# SH3-CONTROLS.net
KiCad netlist of a schematic drawn in Altium Designer
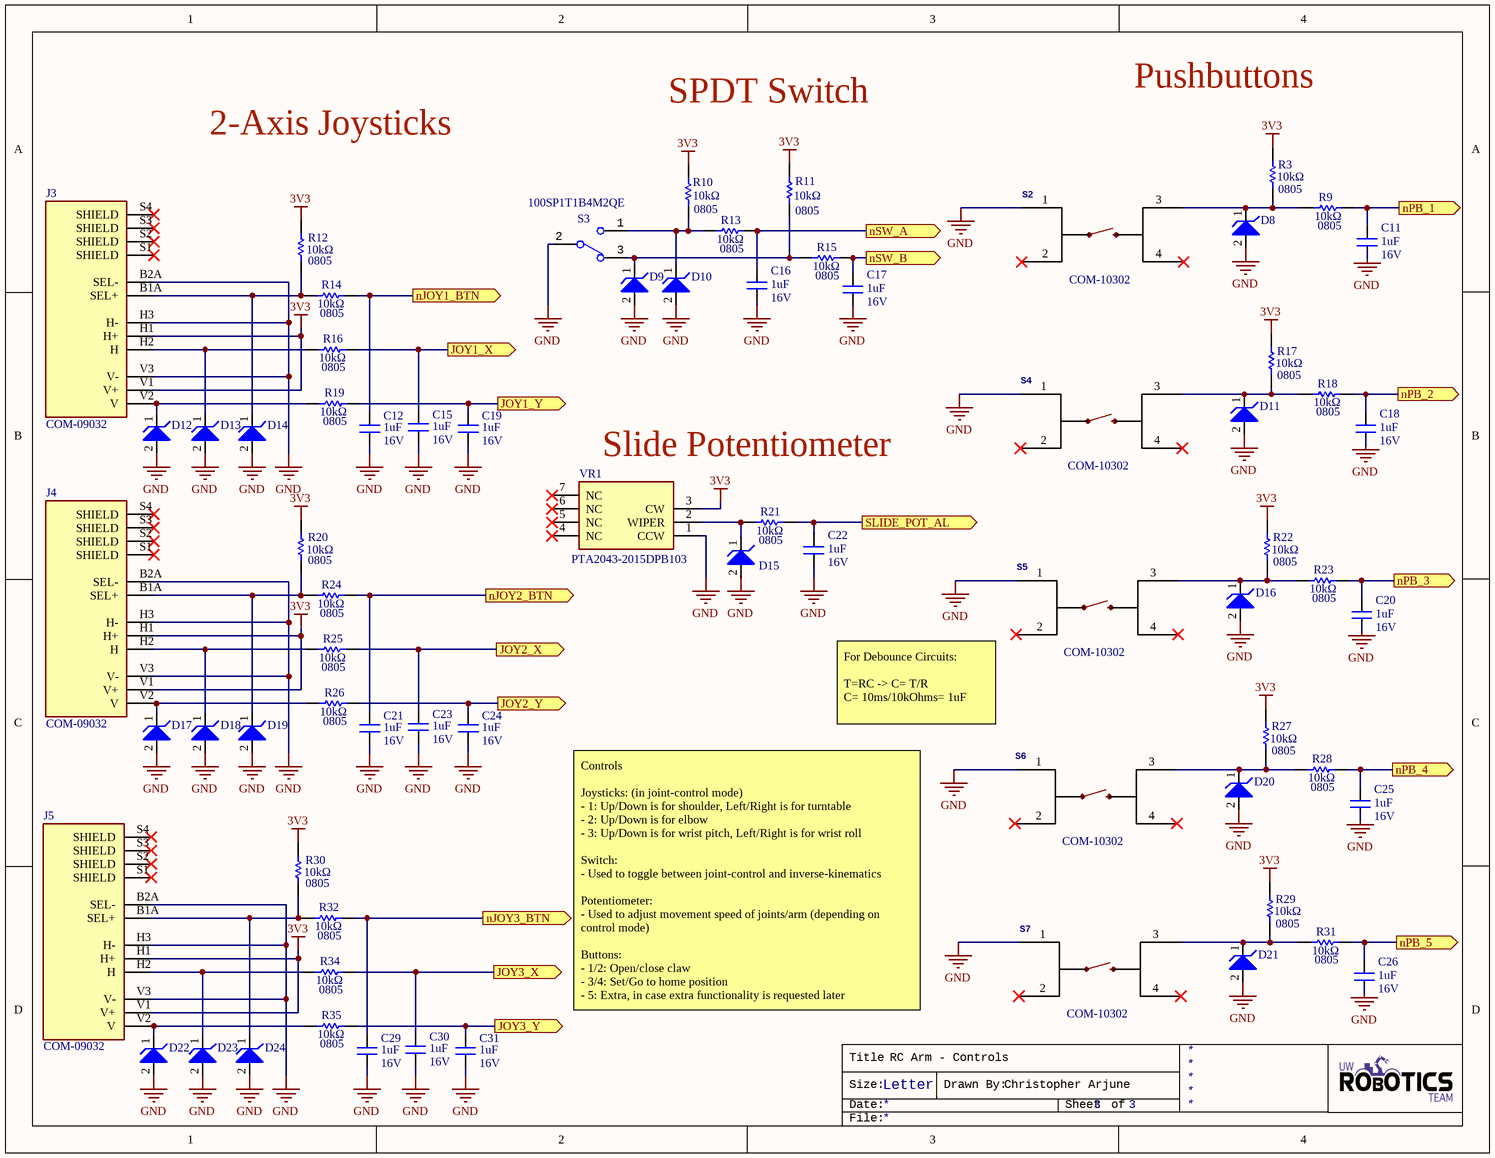
[diagram p0: SH3-CONTROLS.SchDoc]

(export (version "E")
  (design (tool "Eeschema 10.0.6"))
  (components
    (comp (ref "C11")
      (value "1uF")
      (footprint "CAPC2012X140N")
      (description "CAP CER 1UF 16V X7R 0805")
      (fields
        (field (name "TOLERANCE") "10%")
        (field (name "VOLTAGE RATING") "16V")
        (field (name "Comment") "CAP_1uF_16V_0805")
      )
      (libsource (lib "UWRT_Schematic_Library_2020") (part "CAP_1uF_16V_0805"))
    )
    (comp (ref "C12")
      (value "1uF")
      (footprint "CAPC2012X140N")
      (description "CAP CER 1UF 16V X7R 0805")
      (fields
        (field (name "TOLERANCE") "10%")
        (field (name "VOLTAGE RATING") "16V")
        (field (name "Comment") "CAP_1uF_16V_0805")
      )
      (libsource (lib "UWRT_Schematic_Library_2020") (part "CAP_1uF_16V_0805"))
    )
    (comp (ref "C15")
      (value "1uF")
      (footprint "CAPC2012X140N")
      (description "CAP CER 1UF 16V X7R 0805")
      (fields
        (field (name "TOLERANCE") "10%")
        (field (name "VOLTAGE RATING") "16V")
        (field (name "Comment") "CAP_1uF_16V_0805")
      )
      (libsource (lib "UWRT_Schematic_Library_2020") (part "CAP_1uF_16V_0805"))
    )
    (comp (ref "C16")
      (value "1uF")
      (footprint "CAPC2012X140N")
      (description "CAP CER 1UF 16V X7R 0805")
      (fields
        (field (name "TOLERANCE") "10%")
        (field (name "VOLTAGE RATING") "16V")
        (field (name "Comment") "CAP_1uF_16V_0805")
      )
      (libsource (lib "UWRT_Schematic_Library_2020") (part "CAP_1uF_16V_0805"))
    )
    (comp (ref "C17")
      (value "1uF")
      (footprint "CAPC2012X140N")
      (description "CAP CER 1UF 16V X7R 0805")
      (fields
        (field (name "TOLERANCE") "10%")
        (field (name "VOLTAGE RATING") "16V")
        (field (name "Comment") "CAP_1uF_16V_0805")
      )
      (libsource (lib "UWRT_Schematic_Library_2020") (part "CAP_1uF_16V_0805"))
    )
    (comp (ref "C18")
      (value "1uF")
      (footprint "CAPC2012X140N")
      (description "CAP CER 1UF 16V X7R 0805")
      (fields
        (field (name "TOLERANCE") "10%")
        (field (name "VOLTAGE RATING") "16V")
        (field (name "Comment") "CAP_1uF_16V_0805")
      )
      (libsource (lib "UWRT_Schematic_Library_2020") (part "CAP_1uF_16V_0805"))
    )
    (comp (ref "C19")
      (value "1uF")
      (footprint "CAPC2012X140N")
      (description "CAP CER 1UF 16V X7R 0805")
      (fields
        (field (name "TOLERANCE") "10%")
        (field (name "VOLTAGE RATING") "16V")
        (field (name "Comment") "CAP_1uF_16V_0805")
      )
      (libsource (lib "UWRT_Schematic_Library_2020") (part "CAP_1uF_16V_0805"))
    )
    (comp (ref "C20")
      (value "1uF")
      (footprint "CAPC2012X140N")
      (description "CAP CER 1UF 16V X7R 0805")
      (fields
        (field (name "TOLERANCE") "10%")
        (field (name "VOLTAGE RATING") "16V")
        (field (name "Comment") "CAP_1uF_16V_0805")
      )
      (libsource (lib "UWRT_Schematic_Library_2020") (part "CAP_1uF_16V_0805"))
    )
    (comp (ref "C21")
      (value "1uF")
      (footprint "CAPC2012X140N")
      (description "CAP CER 1UF 16V X7R 0805")
      (fields
        (field (name "TOLERANCE") "10%")
        (field (name "VOLTAGE RATING") "16V")
        (field (name "Comment") "CAP_1uF_16V_0805")
      )
      (libsource (lib "UWRT_Schematic_Library_2020") (part "CAP_1uF_16V_0805"))
    )
    (comp (ref "C22")
      (value "1uF")
      (footprint "CAPC2012X140N")
      (description "CAP CER 1UF 16V X7R 0805")
      (fields
        (field (name "TOLERANCE") "10%")
        (field (name "VOLTAGE RATING") "16V")
        (field (name "Comment") "CAP_1uF_16V_0805")
      )
      (libsource (lib "UWRT_Schematic_Library_2020") (part "CAP_1uF_16V_0805"))
    )
    (comp (ref "C23")
      (value "1uF")
      (footprint "CAPC2012X140N")
      (description "CAP CER 1UF 16V X7R 0805")
      (fields
        (field (name "TOLERANCE") "10%")
        (field (name "VOLTAGE RATING") "16V")
        (field (name "Comment") "CAP_1uF_16V_0805")
      )
      (libsource (lib "UWRT_Schematic_Library_2020") (part "CAP_1uF_16V_0805"))
    )
    (comp (ref "C24")
      (value "1uF")
      (footprint "CAPC2012X140N")
      (description "CAP CER 1UF 16V X7R 0805")
      (fields
        (field (name "TOLERANCE") "10%")
        (field (name "VOLTAGE RATING") "16V")
        (field (name "Comment") "CAP_1uF_16V_0805")
      )
      (libsource (lib "UWRT_Schematic_Library_2020") (part "CAP_1uF_16V_0805"))
    )
    (comp (ref "C25")
      (value "1uF")
      (footprint "CAPC2012X140N")
      (description "CAP CER 1UF 16V X7R 0805")
      (fields
        (field (name "TOLERANCE") "10%")
        (field (name "VOLTAGE RATING") "16V")
        (field (name "Comment") "CAP_1uF_16V_0805")
      )
      (libsource (lib "UWRT_Schematic_Library_2020") (part "CAP_1uF_16V_0805"))
    )
    (comp (ref "C26")
      (value "1uF")
      (footprint "CAPC2012X140N")
      (description "CAP CER 1UF 16V X7R 0805")
      (fields
        (field (name "TOLERANCE") "10%")
        (field (name "VOLTAGE RATING") "16V")
        (field (name "Comment") "CAP_1uF_16V_0805")
      )
      (libsource (lib "UWRT_Schematic_Library_2020") (part "CAP_1uF_16V_0805"))
    )
    (comp (ref "C29")
      (value "1uF")
      (footprint "CAPC2012X140N")
      (description "CAP CER 1UF 16V X7R 0805")
      (fields
        (field (name "TOLERANCE") "10%")
        (field (name "VOLTAGE RATING") "16V")
        (field (name "Comment") "CAP_1uF_16V_0805")
      )
      (libsource (lib "UWRT_Schematic_Library_2020") (part "CAP_1uF_16V_0805"))
    )
    (comp (ref "C30")
      (value "1uF")
      (footprint "CAPC2012X140N")
      (description "CAP CER 1UF 16V X7R 0805")
      (fields
        (field (name "TOLERANCE") "10%")
        (field (name "VOLTAGE RATING") "16V")
        (field (name "Comment") "CAP_1uF_16V_0805")
      )
      (libsource (lib "UWRT_Schematic_Library_2020") (part "CAP_1uF_16V_0805"))
    )
    (comp (ref "C31")
      (value "1uF")
      (footprint "CAPC2012X140N")
      (description "CAP CER 1UF 16V X7R 0805")
      (fields
        (field (name "TOLERANCE") "10%")
        (field (name "VOLTAGE RATING") "16V")
        (field (name "Comment") "CAP_1uF_16V_0805")
      )
      (libsource (lib "UWRT_Schematic_Library_2020") (part "CAP_1uF_16V_0805"))
    )
    (comp (ref "D8")
      (value "TVS_DIODE_UNIDIR_3.3V")
      (footprint "SOD523")
      (description "TVS DIODE 3.3V 14.1V SOD523. Used to protect each connector input line going into the MCU.")
      (libsource (lib "UWRT_Schematic_Library_2020") (part "TVS_DIODE_UNIDIR_3.3V"))
    )
    (comp (ref "D9")
      (value "TVS_DIODE_UNIDIR_3.3V")
      (footprint "SOD523")
      (description "TVS DIODE 3.3V 14.1V SOD523. Used to protect each connector input line going into the MCU.")
      (libsource (lib "UWRT_Schematic_Library_2020") (part "TVS_DIODE_UNIDIR_3.3V"))
    )
    (comp (ref "D10")
      (value "TVS_DIODE_UNIDIR_3.3V")
      (footprint "SOD523")
      (description "TVS DIODE 3.3V 14.1V SOD523. Used to protect each connector input line going into the MCU.")
      (libsource (lib "UWRT_Schematic_Library_2020") (part "TVS_DIODE_UNIDIR_3.3V"))
    )
    (comp (ref "D11")
      (value "TVS_DIODE_UNIDIR_3.3V")
      (footprint "SOD523")
      (description "TVS DIODE 3.3V 14.1V SOD523. Used to protect each connector input line going into the MCU.")
      (libsource (lib "UWRT_Schematic_Library_2020") (part "TVS_DIODE_UNIDIR_3.3V"))
    )
    (comp (ref "D12")
      (value "TVS_DIODE_UNIDIR_3.3V")
      (footprint "SOD523")
      (description "TVS DIODE 3.3V 14.1V SOD523. Used to protect each connector input line going into the MCU.")
      (libsource (lib "UWRT_Schematic_Library_2020") (part "TVS_DIODE_UNIDIR_3.3V"))
    )
    (comp (ref "D13")
      (value "TVS_DIODE_UNIDIR_3.3V")
      (footprint "SOD523")
      (description "TVS DIODE 3.3V 14.1V SOD523. Used to protect each connector input line going into the MCU.")
      (libsource (lib "UWRT_Schematic_Library_2020") (part "TVS_DIODE_UNIDIR_3.3V"))
    )
    (comp (ref "D14")
      (value "TVS_DIODE_UNIDIR_3.3V")
      (footprint "SOD523")
      (description "TVS DIODE 3.3V 14.1V SOD523. Used to protect each connector input line going into the MCU.")
      (libsource (lib "UWRT_Schematic_Library_2020") (part "TVS_DIODE_UNIDIR_3.3V"))
    )
    (comp (ref "D15")
      (value "TVS_DIODE_UNIDIR_3.3V")
      (footprint "SOD523")
      (description "TVS DIODE 3.3V 14.1V SOD523. Used to protect each connector input line going into the MCU.")
      (libsource (lib "UWRT_Schematic_Library_2020") (part "TVS_DIODE_UNIDIR_3.3V"))
    )
    (comp (ref "D16")
      (value "TVS_DIODE_UNIDIR_3.3V")
      (footprint "SOD523")
      (description "TVS DIODE 3.3V 14.1V SOD523. Used to protect each connector input line going into the MCU.")
      (libsource (lib "UWRT_Schematic_Library_2020") (part "TVS_DIODE_UNIDIR_3.3V"))
    )
    (comp (ref "D17")
      (value "TVS_DIODE_UNIDIR_3.3V")
      (footprint "SOD523")
      (description "TVS DIODE 3.3V 14.1V SOD523. Used to protect each connector input line going into the MCU.")
      (libsource (lib "UWRT_Schematic_Library_2020") (part "TVS_DIODE_UNIDIR_3.3V"))
    )
    (comp (ref "D18")
      (value "TVS_DIODE_UNIDIR_3.3V")
      (footprint "SOD523")
      (description "TVS DIODE 3.3V 14.1V SOD523. Used to protect each connector input line going into the MCU.")
      (libsource (lib "UWRT_Schematic_Library_2020") (part "TVS_DIODE_UNIDIR_3.3V"))
    )
    (comp (ref "D19")
      (value "TVS_DIODE_UNIDIR_3.3V")
      (footprint "SOD523")
      (description "TVS DIODE 3.3V 14.1V SOD523. Used to protect each connector input line going into the MCU.")
      (libsource (lib "UWRT_Schematic_Library_2020") (part "TVS_DIODE_UNIDIR_3.3V"))
    )
    (comp (ref "D20")
      (value "TVS_DIODE_UNIDIR_3.3V")
      (footprint "SOD523")
      (description "TVS DIODE 3.3V 14.1V SOD523. Used to protect each connector input line going into the MCU.")
      (libsource (lib "UWRT_Schematic_Library_2020") (part "TVS_DIODE_UNIDIR_3.3V"))
    )
    (comp (ref "D21")
      (value "TVS_DIODE_UNIDIR_3.3V")
      (footprint "SOD523")
      (description "TVS DIODE 3.3V 14.1V SOD523. Used to protect each connector input line going into the MCU.")
      (libsource (lib "UWRT_Schematic_Library_2020") (part "TVS_DIODE_UNIDIR_3.3V"))
    )
    (comp (ref "D22")
      (value "TVS_DIODE_UNIDIR_3.3V")
      (footprint "SOD523")
      (description "TVS DIODE 3.3V 14.1V SOD523. Used to protect each connector input line going into the MCU.")
      (libsource (lib "UWRT_Schematic_Library_2020") (part "TVS_DIODE_UNIDIR_3.3V"))
    )
    (comp (ref "D23")
      (value "TVS_DIODE_UNIDIR_3.3V")
      (footprint "SOD523")
      (description "TVS DIODE 3.3V 14.1V SOD523. Used to protect each connector input line going into the MCU.")
      (libsource (lib "UWRT_Schematic_Library_2020") (part "TVS_DIODE_UNIDIR_3.3V"))
    )
    (comp (ref "D24")
      (value "TVS_DIODE_UNIDIR_3.3V")
      (footprint "SOD523")
      (description "TVS DIODE 3.3V 14.1V SOD523. Used to protect each connector input line going into the MCU.")
      (libsource (lib "UWRT_Schematic_Library_2020") (part "TVS_DIODE_UNIDIR_3.3V"))
    )
    (comp (ref "J3")
      (value "2_AXIS_JOYSTICK")
      (footprint "2_AXIS_JOY")
      (description "JOYSTICK 10K OHM 2 AXIS TH")
      (fields (field (name "MANUFACTURER PART NUMBER 1") "COM-09032"))
      (libsource (lib "UWRT_Schematic_Library_2020") (part "2_AXIS_JOYSTICK"))
    )
    (comp (ref "J4")
      (value "2_AXIS_JOYSTICK")
      (footprint "2_AXIS_JOY")
      (description "JOYSTICK 10K OHM 2 AXIS TH")
      (fields (field (name "MANUFACTURER PART NUMBER 1") "COM-09032"))
      (libsource (lib "UWRT_Schematic_Library_2020") (part "2_AXIS_JOYSTICK"))
    )
    (comp (ref "J5")
      (value "2_AXIS_JOYSTICK")
      (footprint "2_AXIS_JOY")
      (description "JOYSTICK 10K OHM 2 AXIS TH")
      (fields (field (name "MANUFACTURER PART NUMBER 1") "COM-09032"))
      (libsource (lib "UWRT_Schematic_Library_2020") (part "2_AXIS_JOYSTICK"))
    )
    (comp (ref "R3")
      (value "10kΩ")
      (footprint "RESC2012X60N")
      (description "RES SMD 10K OHM 1% 1/8W 0805")
      (fields
        (field (name "TOLERANCE") "1%")
        (field (name "CASE CODE (IMPERIAL)") "0805")
        (field (name "Comment") "RES_10kΩ_0805")
      )
      (libsource (lib "UWRT_Schematic_Library_2020") (part "RES_10kΩ_0805"))
    )
    (comp (ref "R9")
      (value "10kΩ")
      (footprint "RESC2012X60N")
      (description "RES SMD 10K OHM 1% 1/8W 0805")
      (fields
        (field (name "CASE CODE (IMPERIAL)") "0805")
        (field (name "TOLERANCE") "1%")
        (field (name "Comment") "RES_10kΩ_0805")
      )
      (libsource (lib "UWRT_Schematic_Library_2020") (part "RES_10kΩ_0805"))
    )
    (comp (ref "R10")
      (value "10kΩ")
      (footprint "RESC2012X60N")
      (description "RES SMD 10K OHM 1% 1/8W 0805")
      (fields
        (field (name "TOLERANCE") "1%")
        (field (name "CASE CODE (IMPERIAL)") "0805")
        (field (name "Comment") "RES_10kΩ_0805")
      )
      (libsource (lib "UWRT_Schematic_Library_2020") (part "RES_10kΩ_0805"))
    )
    (comp (ref "R11")
      (value "10kΩ")
      (footprint "RESC2012X60N")
      (description "RES SMD 10K OHM 1% 1/8W 0805")
      (fields
        (field (name "TOLERANCE") "1%")
        (field (name "CASE CODE (IMPERIAL)") "0805")
        (field (name "Comment") "RES_10kΩ_0805")
      )
      (libsource (lib "UWRT_Schematic_Library_2020") (part "RES_10kΩ_0805"))
    )
    (comp (ref "R12")
      (value "10kΩ")
      (footprint "RESC2012X60N")
      (description "RES SMD 10K OHM 1% 1/8W 0805")
      (fields
        (field (name "TOLERANCE") "1%")
        (field (name "CASE CODE (IMPERIAL)") "0805")
        (field (name "Comment") "RES_10kΩ_0805")
      )
      (libsource (lib "UWRT_Schematic_Library_2020") (part "RES_10kΩ_0805"))
    )
    (comp (ref "R13")
      (value "10kΩ")
      (footprint "RESC2012X60N")
      (description "RES SMD 10K OHM 1% 1/8W 0805")
      (fields
        (field (name "CASE CODE (IMPERIAL)") "0805")
        (field (name "TOLERANCE") "1%")
        (field (name "Comment") "RES_10kΩ_0805")
      )
      (libsource (lib "UWRT_Schematic_Library_2020") (part "RES_10kΩ_0805"))
    )
    (comp (ref "R14")
      (value "10kΩ")
      (footprint "RESC2012X60N")
      (description "RES SMD 10K OHM 1% 1/8W 0805")
      (fields
        (field (name "CASE CODE (IMPERIAL)") "0805")
        (field (name "TOLERANCE") "1%")
        (field (name "Comment") "RES_10kΩ_0805")
      )
      (libsource (lib "UWRT_Schematic_Library_2020") (part "RES_10kΩ_0805"))
    )
    (comp (ref "R15")
      (value "10kΩ")
      (footprint "RESC2012X60N")
      (description "RES SMD 10K OHM 1% 1/8W 0805")
      (fields
        (field (name "CASE CODE (IMPERIAL)") "0805")
        (field (name "TOLERANCE") "1%")
        (field (name "Comment") "RES_10kΩ_0805")
      )
      (libsource (lib "UWRT_Schematic_Library_2020") (part "RES_10kΩ_0805"))
    )
    (comp (ref "R16")
      (value "10kΩ")
      (footprint "RESC2012X60N")
      (description "RES SMD 10K OHM 1% 1/8W 0805")
      (fields
        (field (name "CASE CODE (IMPERIAL)") "0805")
        (field (name "TOLERANCE") "1%")
        (field (name "Comment") "RES_10kΩ_0805")
      )
      (libsource (lib "UWRT_Schematic_Library_2020") (part "RES_10kΩ_0805"))
    )
    (comp (ref "R17")
      (value "10kΩ")
      (footprint "RESC2012X60N")
      (description "RES SMD 10K OHM 1% 1/8W 0805")
      (fields
        (field (name "TOLERANCE") "1%")
        (field (name "CASE CODE (IMPERIAL)") "0805")
        (field (name "Comment") "RES_10kΩ_0805")
      )
      (libsource (lib "UWRT_Schematic_Library_2020") (part "RES_10kΩ_0805"))
    )
    (comp (ref "R18")
      (value "10kΩ")
      (footprint "RESC2012X60N")
      (description "RES SMD 10K OHM 1% 1/8W 0805")
      (fields
        (field (name "CASE CODE (IMPERIAL)") "0805")
        (field (name "TOLERANCE") "1%")
        (field (name "Comment") "RES_10kΩ_0805")
      )
      (libsource (lib "UWRT_Schematic_Library_2020") (part "RES_10kΩ_0805"))
    )
    (comp (ref "R19")
      (value "10kΩ")
      (footprint "RESC2012X60N")
      (description "RES SMD 10K OHM 1% 1/8W 0805")
      (fields
        (field (name "CASE CODE (IMPERIAL)") "0805")
        (field (name "TOLERANCE") "1%")
        (field (name "Comment") "RES_10kΩ_0805")
      )
      (libsource (lib "UWRT_Schematic_Library_2020") (part "RES_10kΩ_0805"))
    )
    (comp (ref "R20")
      (value "10kΩ")
      (footprint "RESC2012X60N")
      (description "RES SMD 10K OHM 1% 1/8W 0805")
      (fields
        (field (name "TOLERANCE") "1%")
        (field (name "CASE CODE (IMPERIAL)") "0805")
        (field (name "Comment") "RES_10kΩ_0805")
      )
      (libsource (lib "UWRT_Schematic_Library_2020") (part "RES_10kΩ_0805"))
    )
    (comp (ref "R21")
      (value "10kΩ")
      (footprint "RESC2012X60N")
      (description "RES SMD 10K OHM 1% 1/8W 0805")
      (fields
        (field (name "CASE CODE (IMPERIAL)") "0805")
        (field (name "TOLERANCE") "1%")
        (field (name "Comment") "RES_10kΩ_0805")
      )
      (libsource (lib "UWRT_Schematic_Library_2020") (part "RES_10kΩ_0805"))
    )
    (comp (ref "R22")
      (value "10kΩ")
      (footprint "RESC2012X60N")
      (description "RES SMD 10K OHM 1% 1/8W 0805")
      (fields
        (field (name "TOLERANCE") "1%")
        (field (name "CASE CODE (IMPERIAL)") "0805")
        (field (name "Comment") "RES_10kΩ_0805")
      )
      (libsource (lib "UWRT_Schematic_Library_2020") (part "RES_10kΩ_0805"))
    )
    (comp (ref "R23")
      (value "10kΩ")
      (footprint "RESC2012X60N")
      (description "RES SMD 10K OHM 1% 1/8W 0805")
      (fields
        (field (name "CASE CODE (IMPERIAL)") "0805")
        (field (name "TOLERANCE") "1%")
        (field (name "Comment") "RES_10kΩ_0805")
      )
      (libsource (lib "UWRT_Schematic_Library_2020") (part "RES_10kΩ_0805"))
    )
    (comp (ref "R24")
      (value "10kΩ")
      (footprint "RESC2012X60N")
      (description "RES SMD 10K OHM 1% 1/8W 0805")
      (fields
        (field (name "CASE CODE (IMPERIAL)") "0805")
        (field (name "TOLERANCE") "1%")
        (field (name "Comment") "RES_10kΩ_0805")
      )
      (libsource (lib "UWRT_Schematic_Library_2020") (part "RES_10kΩ_0805"))
    )
    (comp (ref "R25")
      (value "10kΩ")
      (footprint "RESC2012X60N")
      (description "RES SMD 10K OHM 1% 1/8W 0805")
      (fields
        (field (name "CASE CODE (IMPERIAL)") "0805")
        (field (name "TOLERANCE") "1%")
        (field (name "Comment") "RES_10kΩ_0805")
      )
      (libsource (lib "UWRT_Schematic_Library_2020") (part "RES_10kΩ_0805"))
    )
    (comp (ref "R26")
      (value "10kΩ")
      (footprint "RESC2012X60N")
      (description "RES SMD 10K OHM 1% 1/8W 0805")
      (fields
        (field (name "CASE CODE (IMPERIAL)") "0805")
        (field (name "TOLERANCE") "1%")
        (field (name "Comment") "RES_10kΩ_0805")
      )
      (libsource (lib "UWRT_Schematic_Library_2020") (part "RES_10kΩ_0805"))
    )
    (comp (ref "R27")
      (value "10kΩ")
      (footprint "RESC2012X60N")
      (description "RES SMD 10K OHM 1% 1/8W 0805")
      (fields
        (field (name "TOLERANCE") "1%")
        (field (name "CASE CODE (IMPERIAL)") "0805")
        (field (name "Comment") "RES_10kΩ_0805")
      )
      (libsource (lib "UWRT_Schematic_Library_2020") (part "RES_10kΩ_0805"))
    )
    (comp (ref "R28")
      (value "10kΩ")
      (footprint "RESC2012X60N")
      (description "RES SMD 10K OHM 1% 1/8W 0805")
      (fields
        (field (name "CASE CODE (IMPERIAL)") "0805")
        (field (name "TOLERANCE") "1%")
        (field (name "Comment") "RES_10kΩ_0805")
      )
      (libsource (lib "UWRT_Schematic_Library_2020") (part "RES_10kΩ_0805"))
    )
    (comp (ref "R29")
      (value "10kΩ")
      (footprint "RESC2012X60N")
      (description "RES SMD 10K OHM 1% 1/8W 0805")
      (fields
        (field (name "TOLERANCE") "1%")
        (field (name "CASE CODE (IMPERIAL)") "0805")
        (field (name "Comment") "RES_10kΩ_0805")
      )
      (libsource (lib "UWRT_Schematic_Library_2020") (part "RES_10kΩ_0805"))
    )
    (comp (ref "R30")
      (value "10kΩ")
      (footprint "RESC2012X60N")
      (description "RES SMD 10K OHM 1% 1/8W 0805")
      (fields
        (field (name "TOLERANCE") "1%")
        (field (name "CASE CODE (IMPERIAL)") "0805")
        (field (name "Comment") "RES_10kΩ_0805")
      )
      (libsource (lib "UWRT_Schematic_Library_2020") (part "RES_10kΩ_0805"))
    )
    (comp (ref "R31")
      (value "10kΩ")
      (footprint "RESC2012X60N")
      (description "RES SMD 10K OHM 1% 1/8W 0805")
      (fields
        (field (name "CASE CODE (IMPERIAL)") "0805")
        (field (name "TOLERANCE") "1%")
        (field (name "Comment") "RES_10kΩ_0805")
      )
      (libsource (lib "UWRT_Schematic_Library_2020") (part "RES_10kΩ_0805"))
    )
    (comp (ref "R32")
      (value "10kΩ")
      (footprint "RESC2012X60N")
      (description "RES SMD 10K OHM 1% 1/8W 0805")
      (fields
        (field (name "CASE CODE (IMPERIAL)") "0805")
        (field (name "TOLERANCE") "1%")
        (field (name "Comment") "RES_10kΩ_0805")
      )
      (libsource (lib "UWRT_Schematic_Library_2020") (part "RES_10kΩ_0805"))
    )
    (comp (ref "R34")
      (value "10kΩ")
      (footprint "RESC2012X60N")
      (description "RES SMD 10K OHM 1% 1/8W 0805")
      (fields
        (field (name "CASE CODE (IMPERIAL)") "0805")
        (field (name "TOLERANCE") "1%")
        (field (name "Comment") "RES_10kΩ_0805")
      )
      (libsource (lib "UWRT_Schematic_Library_2020") (part "RES_10kΩ_0805"))
    )
    (comp (ref "R35")
      (value "10kΩ")
      (footprint "RESC2012X60N")
      (description "RES SMD 10K OHM 1% 1/8W 0805")
      (fields
        (field (name "CASE CODE (IMPERIAL)") "0805")
        (field (name "TOLERANCE") "1%")
        (field (name "Comment") "RES_10kΩ_0805")
      )
      (libsource (lib "UWRT_Schematic_Library_2020") (part "RES_10kΩ_0805"))
    )
    (comp (ref "S2")
      (value "Pushbutton")
      (footprint "TACTILE_SWITCH_PTH_12MM")
      (description "Momentary Switch (Pushbutton) - SPST")
      (fields (field (name "MANUFACTURER PART NUMBER 1") "COM-10302"))
      (libsource (lib "UWRT_Schematic_Library_2020") (part "MOMENTARY_SWITCH_TH"))
    )
    (comp (ref "S3")
      (value "SW_SPDT")
      (footprint "100SP1T1B4M2QE")
      (description "SWITCH TOGGLE SPDT 5A 120V")
      (fields (field (name "MANUFACTURER PART NUMBER 1") "100SP1T1B4M2QE"))
      (libsource (lib "UWRT_Schematic_Library_2020") (part "SW_SPDT"))
    )
    (comp (ref "S4")
      (value "Pushbutton")
      (footprint "TACTILE_SWITCH_PTH_12MM")
      (description "Momentary Switch (Pushbutton) - SPST")
      (fields (field (name "MANUFACTURER PART NUMBER 1") "COM-10302"))
      (libsource (lib "UWRT_Schematic_Library_2020") (part "MOMENTARY_SWITCH_TH"))
    )
    (comp (ref "S5")
      (value "Pushbutton")
      (footprint "TACTILE_SWITCH_PTH_12MM")
      (description "Momentary Switch (Pushbutton) - SPST")
      (fields (field (name "MANUFACTURER PART NUMBER 1") "COM-10302"))
      (libsource (lib "UWRT_Schematic_Library_2020") (part "MOMENTARY_SWITCH_TH"))
    )
    (comp (ref "S6")
      (value "Pushbutton")
      (footprint "TACTILE_SWITCH_PTH_12MM")
      (description "Momentary Switch (Pushbutton) - SPST")
      (fields (field (name "MANUFACTURER PART NUMBER 1") "COM-10302"))
      (libsource (lib "UWRT_Schematic_Library_2020") (part "MOMENTARY_SWITCH_TH"))
    )
    (comp (ref "S7")
      (value "Pushbutton")
      (footprint "TACTILE_SWITCH_PTH_12MM")
      (description "Momentary Switch (Pushbutton) - SPST")
      (fields (field (name "MANUFACTURER PART NUMBER 1") "COM-10302"))
      (libsource (lib "UWRT_Schematic_Library_2020") (part "MOMENTARY_SWITCH_TH"))
    )
    (comp (ref "VR1")
      (value "POT_10K_SLIDE")
      (footprint "PTA20432015CPB103")
      (description "SLIDE POT 10K OHM 0.1W TOP 20MM")
      (fields
        (field (name "MANUFACTURER PART NUMBER 1") "PTA2043-2015DPB103")
        (field (name "TOLERANCE") "20%")
      )
      (libsource (lib "UWRT_Schematic_Library_2020") (part "POT_10K_SLIDE"))
    )
  )
  (nets
    (net (code "1") (name "/JOY1_X") (class "Default")
      (node (ref "C15") (pin "2") (pinfunction "2_2") (pintype "passive"))
      (node (ref "R16") (pin "2") (pinfunction "2_2") (pintype "passive"))
    )
    (net (code "2") (name "/JOY1_Y") (class "Default")
      (node (ref "C19") (pin "2") (pinfunction "2_2") (pintype "passive"))
      (node (ref "R19") (pin "2") (pinfunction "2_2") (pintype "passive"))
    )
    (net (code "3") (name "/JOY2_X") (class "Default")
      (node (ref "C23") (pin "2") (pinfunction "2_2") (pintype "passive"))
      (node (ref "R25") (pin "2") (pinfunction "2_2") (pintype "passive"))
    )
    (net (code "4") (name "/JOY2_Y") (class "Default")
      (node (ref "C24") (pin "2") (pinfunction "2_2") (pintype "passive"))
      (node (ref "R26") (pin "2") (pinfunction "2_2") (pintype "passive"))
    )
    (net (code "5") (name "/JOY3_X") (class "Default")
      (node (ref "C30") (pin "2") (pinfunction "2_2") (pintype "passive"))
      (node (ref "R34") (pin "2") (pinfunction "2_2") (pintype "passive"))
    )
    (net (code "6") (name "/JOY3_Y") (class "Default")
      (node (ref "C31") (pin "2") (pinfunction "2_2") (pintype "passive"))
      (node (ref "R35") (pin "2") (pinfunction "2_2") (pintype "passive"))
    )
    (net (code "7") (name "/SLIDE_POT_AL") (class "Default")
      (node (ref "C22") (pin "2") (pinfunction "2_2") (pintype "passive"))
      (node (ref "R21") (pin "2") (pinfunction "2_2") (pintype "passive"))
    )
    (net (code "8") (name "/nJOY1_BTN") (class "Default")
      (node (ref "C12") (pin "2") (pinfunction "2_2") (pintype "passive"))
      (node (ref "R14") (pin "2") (pinfunction "2_2") (pintype "passive"))
    )
    (net (code "9") (name "/nJOY2_BTN") (class "Default")
      (node (ref "C21") (pin "2") (pinfunction "2_2") (pintype "passive"))
      (node (ref "R24") (pin "2") (pinfunction "2_2") (pintype "passive"))
    )
    (net (code "10") (name "/nJOY3_BTN") (class "Default")
      (node (ref "C29") (pin "2") (pinfunction "2_2") (pintype "passive"))
      (node (ref "R32") (pin "2") (pinfunction "2_2") (pintype "passive"))
    )
    (net (code "11") (name "/nPB_1") (class "Default")
      (node (ref "C11") (pin "2") (pinfunction "2_2") (pintype "passive"))
      (node (ref "R9") (pin "2") (pinfunction "2_2") (pintype "passive"))
    )
    (net (code "12") (name "/nPB_2") (class "Default")
      (node (ref "C18") (pin "2") (pinfunction "2_2") (pintype "passive"))
      (node (ref "R18") (pin "2") (pinfunction "2_2") (pintype "passive"))
    )
    (net (code "13") (name "/nPB_3") (class "Default")
      (node (ref "C20") (pin "2") (pinfunction "2_2") (pintype "passive"))
      (node (ref "R23") (pin "2") (pinfunction "2_2") (pintype "passive"))
    )
    (net (code "14") (name "/nPB_4") (class "Default")
      (node (ref "C25") (pin "2") (pinfunction "2_2") (pintype "passive"))
      (node (ref "R28") (pin "2") (pinfunction "2_2") (pintype "passive"))
    )
    (net (code "15") (name "/nPB_5") (class "Default")
      (node (ref "C26") (pin "2") (pinfunction "2_2") (pintype "passive"))
      (node (ref "R31") (pin "2") (pinfunction "2_2") (pintype "passive"))
    )
    (net (code "16") (name "/nSW_A") (class "Default")
      (node (ref "C16") (pin "2") (pinfunction "2_2") (pintype "passive"))
      (node (ref "R13") (pin "2") (pinfunction "2_2") (pintype "passive"))
    )
    (net (code "17") (name "/nSW_B") (class "Default")
      (node (ref "C17") (pin "2") (pinfunction "2_2") (pintype "passive"))
      (node (ref "R15") (pin "2") (pinfunction "2_2") (pintype "passive"))
    )
    (net (code "18") (name "3V3") (class "Default")
      (node (ref "J3") (pin "H1") (pinfunction "H+_H1") (pintype "passive"))
      (node (ref "J3") (pin "V1") (pinfunction "V+_V1") (pintype "passive"))
      (node (ref "J4") (pin "H1") (pinfunction "H+_H1") (pintype "passive"))
      (node (ref "J4") (pin "V1") (pinfunction "V+_V1") (pintype "passive"))
      (node (ref "J5") (pin "H1") (pinfunction "H+_H1") (pintype "passive"))
      (node (ref "J5") (pin "V1") (pinfunction "V+_V1") (pintype "passive"))
      (node (ref "R10") (pin "1") (pinfunction "1_1") (pintype "passive"))
      (node (ref "R11") (pin "1") (pinfunction "1_1") (pintype "passive"))
      (node (ref "R12") (pin "1") (pinfunction "1_1") (pintype "passive"))
      (node (ref "R17") (pin "1") (pinfunction "1_1") (pintype "passive"))
      (node (ref "R20") (pin "1") (pinfunction "1_1") (pintype "passive"))
      (node (ref "R22") (pin "1") (pinfunction "1_1") (pintype "passive"))
      (node (ref "R27") (pin "1") (pinfunction "1_1") (pintype "passive"))
      (node (ref "R29") (pin "1") (pinfunction "1_1") (pintype "passive"))
      (node (ref "R3") (pin "1") (pinfunction "1_1") (pintype "passive"))
      (node (ref "R30") (pin "1") (pinfunction "1_1") (pintype "passive"))
      (node (ref "VR1") (pin "3") (pinfunction "CW_3") (pintype "passive"))
    )
    (net (code "19") (name "GND") (class "Default")
      (node (ref "C11") (pin "1") (pinfunction "1_1") (pintype "passive"))
      (node (ref "C12") (pin "1") (pinfunction "1_1") (pintype "passive"))
      (node (ref "C15") (pin "1") (pinfunction "1_1") (pintype "passive"))
      (node (ref "C16") (pin "1") (pinfunction "1_1") (pintype "passive"))
      (node (ref "C17") (pin "1") (pinfunction "1_1") (pintype "passive"))
      (node (ref "C18") (pin "1") (pinfunction "1_1") (pintype "passive"))
      (node (ref "C19") (pin "1") (pinfunction "1_1") (pintype "passive"))
      (node (ref "C20") (pin "1") (pinfunction "1_1") (pintype "passive"))
      (node (ref "C21") (pin "1") (pinfunction "1_1") (pintype "passive"))
      (node (ref "C22") (pin "1") (pinfunction "1_1") (pintype "passive"))
      (node (ref "C23") (pin "1") (pinfunction "1_1") (pintype "passive"))
      (node (ref "C24") (pin "1") (pinfunction "1_1") (pintype "passive"))
      (node (ref "C25") (pin "1") (pinfunction "1_1") (pintype "passive"))
      (node (ref "C26") (pin "1") (pinfunction "1_1") (pintype "passive"))
      (node (ref "C29") (pin "1") (pinfunction "1_1") (pintype "passive"))
      (node (ref "C30") (pin "1") (pinfunction "1_1") (pintype "passive"))
      (node (ref "C31") (pin "1") (pinfunction "1_1") (pintype "passive"))
      (node (ref "D10") (pin "2") (pinfunction "2_2") (pintype "passive"))
      (node (ref "D11") (pin "2") (pinfunction "2_2") (pintype "passive"))
      (node (ref "D12") (pin "2") (pinfunction "2_2") (pintype "passive"))
      (node (ref "D13") (pin "2") (pinfunction "2_2") (pintype "passive"))
      (node (ref "D14") (pin "2") (pinfunction "2_2") (pintype "passive"))
      (node (ref "D15") (pin "2") (pinfunction "2_2") (pintype "passive"))
      (node (ref "D16") (pin "2") (pinfunction "2_2") (pintype "passive"))
      (node (ref "D17") (pin "2") (pinfunction "2_2") (pintype "passive"))
      (node (ref "D18") (pin "2") (pinfunction "2_2") (pintype "passive"))
      (node (ref "D19") (pin "2") (pinfunction "2_2") (pintype "passive"))
      (node (ref "D20") (pin "2") (pinfunction "2_2") (pintype "passive"))
      (node (ref "D21") (pin "2") (pinfunction "2_2") (pintype "passive"))
      (node (ref "D22") (pin "2") (pinfunction "2_2") (pintype "passive"))
      (node (ref "D23") (pin "2") (pinfunction "2_2") (pintype "passive"))
      (node (ref "D24") (pin "2") (pinfunction "2_2") (pintype "passive"))
      (node (ref "D8") (pin "2") (pinfunction "2_2") (pintype "passive"))
      (node (ref "D9") (pin "2") (pinfunction "2_2") (pintype "passive"))
      (node (ref "J3") (pin "B2A") (pinfunction "SEL-_B2A") (pintype "passive"))
      (node (ref "J3") (pin "H3") (pinfunction "H-_H3") (pintype "passive"))
      (node (ref "J3") (pin "V3") (pinfunction "V-_V3") (pintype "passive"))
      (node (ref "J4") (pin "B2A") (pinfunction "SEL-_B2A") (pintype "passive"))
      (node (ref "J4") (pin "H3") (pinfunction "H-_H3") (pintype "passive"))
      (node (ref "J4") (pin "V3") (pinfunction "V-_V3") (pintype "passive"))
      (node (ref "J5") (pin "B2A") (pinfunction "SEL-_B2A") (pintype "passive"))
      (node (ref "J5") (pin "H3") (pinfunction "H-_H3") (pintype "passive"))
      (node (ref "J5") (pin "V3") (pinfunction "V-_V3") (pintype "passive"))
      (node (ref "S2") (pin "1") (pinfunction "1_1") (pintype "passive"))
      (node (ref "S3") (pin "2") (pinfunction "2_2") (pintype "passive"))
      (node (ref "S4") (pin "1") (pinfunction "1_1") (pintype "passive"))
      (node (ref "S5") (pin "1") (pinfunction "1_1") (pintype "passive"))
      (node (ref "S6") (pin "1") (pinfunction "1_1") (pintype "passive"))
      (node (ref "S7") (pin "1") (pinfunction "1_1") (pintype "passive"))
      (node (ref "VR1") (pin "1") (pinfunction "CCW_1") (pintype "passive"))
    )
    (net (code "20") (name "Net-(D8-Pad1)") (class "Default")
      (node (ref "D8") (pin "1") (pinfunction "1_1") (pintype "passive"))
      (node (ref "R3") (pin "2") (pinfunction "2_2") (pintype "passive"))
      (node (ref "R9") (pin "1") (pinfunction "1_1") (pintype "passive"))
      (node (ref "S2") (pin "3") (pinfunction "3_3") (pintype "passive"))
    )
    (net (code "21") (name "Net-(D9-Pad1)") (class "Default")
      (node (ref "D9") (pin "1") (pinfunction "1_1") (pintype "passive"))
      (node (ref "R11") (pin "2") (pinfunction "2_2") (pintype "passive"))
      (node (ref "R15") (pin "1") (pinfunction "1_1") (pintype "passive"))
      (node (ref "S3") (pin "3") (pinfunction "3_3") (pintype "passive"))
    )
    (net (code "22") (name "Net-(D10-Pad1)") (class "Default")
      (node (ref "D10") (pin "1") (pinfunction "1_1") (pintype "passive"))
      (node (ref "R10") (pin "2") (pinfunction "2_2") (pintype "passive"))
      (node (ref "R13") (pin "1") (pinfunction "1_1") (pintype "passive"))
      (node (ref "S3") (pin "1") (pinfunction "1_1") (pintype "passive"))
    )
    (net (code "23") (name "Net-(D11-Pad1)") (class "Default")
      (node (ref "D11") (pin "1") (pinfunction "1_1") (pintype "passive"))
      (node (ref "R17") (pin "2") (pinfunction "2_2") (pintype "passive"))
      (node (ref "R18") (pin "1") (pinfunction "1_1") (pintype "passive"))
      (node (ref "S4") (pin "3") (pinfunction "3_3") (pintype "passive"))
    )
    (net (code "24") (name "Net-(D16-Pad1)") (class "Default")
      (node (ref "D16") (pin "1") (pinfunction "1_1") (pintype "passive"))
      (node (ref "R22") (pin "2") (pinfunction "2_2") (pintype "passive"))
      (node (ref "R23") (pin "1") (pinfunction "1_1") (pintype "passive"))
      (node (ref "S5") (pin "3") (pinfunction "3_3") (pintype "passive"))
    )
    (net (code "25") (name "Net-(D20-Pad1)") (class "Default")
      (node (ref "D20") (pin "1") (pinfunction "1_1") (pintype "passive"))
      (node (ref "R27") (pin "2") (pinfunction "2_2") (pintype "passive"))
      (node (ref "R28") (pin "1") (pinfunction "1_1") (pintype "passive"))
      (node (ref "S6") (pin "3") (pinfunction "3_3") (pintype "passive"))
    )
    (net (code "26") (name "Net-(D21-Pad1)") (class "Default")
      (node (ref "D21") (pin "1") (pinfunction "1_1") (pintype "passive"))
      (node (ref "R29") (pin "2") (pinfunction "2_2") (pintype "passive"))
      (node (ref "R31") (pin "1") (pinfunction "1_1") (pintype "passive"))
      (node (ref "S7") (pin "3") (pinfunction "3_3") (pintype "passive"))
    )
    (net (code "27") (name "Net-(J3-H)") (class "Default")
      (node (ref "D13") (pin "1") (pinfunction "1_1") (pintype "passive"))
      (node (ref "J3") (pin "H2") (pinfunction "H_H2") (pintype "passive"))
      (node (ref "R16") (pin "1") (pinfunction "1_1") (pintype "passive"))
    )
    (net (code "28") (name "Net-(J3-SEL+)") (class "Default")
      (node (ref "D14") (pin "1") (pinfunction "1_1") (pintype "passive"))
      (node (ref "J3") (pin "B1A") (pinfunction "SEL+_B1A") (pintype "passive"))
      (node (ref "R12") (pin "2") (pinfunction "2_2") (pintype "passive"))
      (node (ref "R14") (pin "1") (pinfunction "1_1") (pintype "passive"))
    )
    (net (code "29") (name "Net-(J3-V)") (class "Default")
      (node (ref "D12") (pin "1") (pinfunction "1_1") (pintype "passive"))
      (node (ref "J3") (pin "V2") (pinfunction "V_V2") (pintype "passive"))
      (node (ref "R19") (pin "1") (pinfunction "1_1") (pintype "passive"))
    )
    (net (code "30") (name "Net-(J4-H)") (class "Default")
      (node (ref "D18") (pin "1") (pinfunction "1_1") (pintype "passive"))
      (node (ref "J4") (pin "H2") (pinfunction "H_H2") (pintype "passive"))
      (node (ref "R25") (pin "1") (pinfunction "1_1") (pintype "passive"))
    )
    (net (code "31") (name "Net-(J4-SEL+)") (class "Default")
      (node (ref "D19") (pin "1") (pinfunction "1_1") (pintype "passive"))
      (node (ref "J4") (pin "B1A") (pinfunction "SEL+_B1A") (pintype "passive"))
      (node (ref "R20") (pin "2") (pinfunction "2_2") (pintype "passive"))
      (node (ref "R24") (pin "1") (pinfunction "1_1") (pintype "passive"))
    )
    (net (code "32") (name "Net-(J4-V)") (class "Default")
      (node (ref "D17") (pin "1") (pinfunction "1_1") (pintype "passive"))
      (node (ref "J4") (pin "V2") (pinfunction "V_V2") (pintype "passive"))
      (node (ref "R26") (pin "1") (pinfunction "1_1") (pintype "passive"))
    )
    (net (code "33") (name "Net-(J5-H)") (class "Default")
      (node (ref "D23") (pin "1") (pinfunction "1_1") (pintype "passive"))
      (node (ref "J5") (pin "H2") (pinfunction "H_H2") (pintype "passive"))
      (node (ref "R34") (pin "1") (pinfunction "1_1") (pintype "passive"))
    )
    (net (code "34") (name "Net-(J5-SEL+)") (class "Default")
      (node (ref "D24") (pin "1") (pinfunction "1_1") (pintype "passive"))
      (node (ref "J5") (pin "B1A") (pinfunction "SEL+_B1A") (pintype "passive"))
      (node (ref "R30") (pin "2") (pinfunction "2_2") (pintype "passive"))
      (node (ref "R32") (pin "1") (pinfunction "1_1") (pintype "passive"))
    )
    (net (code "35") (name "Net-(J5-V)") (class "Default")
      (node (ref "D22") (pin "1") (pinfunction "1_1") (pintype "passive"))
      (node (ref "J5") (pin "V2") (pinfunction "V_V2") (pintype "passive"))
      (node (ref "R35") (pin "1") (pinfunction "1_1") (pintype "passive"))
    )
    (net (code "36") (name "Net-(VR1-WIPER)") (class "Default")
      (node (ref "D15") (pin "1") (pinfunction "1_1") (pintype "passive"))
      (node (ref "R21") (pin "1") (pinfunction "1_1") (pintype "passive"))
      (node (ref "VR1") (pin "2") (pinfunction "WIPER_2") (pintype "passive"))
    )
    (net (code "37") (name "unconnected-(J3-SHIELD-PadS1)") (class "Default")
      (node (ref "J3") (pin "S1") (pinfunction "SHIELD_S1") (pintype "passive+no_connect"))
    )
    (net (code "38") (name "unconnected-(J3-SHIELD-PadS2)") (class "Default")
      (node (ref "J3") (pin "S2") (pinfunction "SHIELD_S2") (pintype "passive+no_connect"))
    )
    (net (code "39") (name "unconnected-(J3-SHIELD-PadS3)") (class "Default")
      (node (ref "J3") (pin "S3") (pinfunction "SHIELD_S3") (pintype "passive+no_connect"))
    )
    (net (code "40") (name "unconnected-(J3-SHIELD-PadS4)") (class "Default")
      (node (ref "J3") (pin "S4") (pinfunction "SHIELD_S4") (pintype "passive+no_connect"))
    )
    (net (code "41") (name "unconnected-(J4-SHIELD-PadS1)") (class "Default")
      (node (ref "J4") (pin "S1") (pinfunction "SHIELD_S1") (pintype "passive+no_connect"))
    )
    (net (code "42") (name "unconnected-(J4-SHIELD-PadS2)") (class "Default")
      (node (ref "J4") (pin "S2") (pinfunction "SHIELD_S2") (pintype "passive+no_connect"))
    )
    (net (code "43") (name "unconnected-(J4-SHIELD-PadS3)") (class "Default")
      (node (ref "J4") (pin "S3") (pinfunction "SHIELD_S3") (pintype "passive+no_connect"))
    )
    (net (code "44") (name "unconnected-(J4-SHIELD-PadS4)") (class "Default")
      (node (ref "J4") (pin "S4") (pinfunction "SHIELD_S4") (pintype "passive+no_connect"))
    )
    (net (code "45") (name "unconnected-(J5-SHIELD-PadS1)") (class "Default")
      (node (ref "J5") (pin "S1") (pinfunction "SHIELD_S1") (pintype "passive+no_connect"))
    )
    (net (code "46") (name "unconnected-(J5-SHIELD-PadS2)") (class "Default")
      (node (ref "J5") (pin "S2") (pinfunction "SHIELD_S2") (pintype "passive+no_connect"))
    )
    (net (code "47") (name "unconnected-(J5-SHIELD-PadS3)") (class "Default")
      (node (ref "J5") (pin "S3") (pinfunction "SHIELD_S3") (pintype "passive+no_connect"))
    )
    (net (code "48") (name "unconnected-(J5-SHIELD-PadS4)") (class "Default")
      (node (ref "J5") (pin "S4") (pinfunction "SHIELD_S4") (pintype "passive+no_connect"))
    )
    (net (code "49") (name "unconnected-(S2-Pad2)") (class "Default")
      (node (ref "S2") (pin "2") (pinfunction "2_2") (pintype "passive+no_connect"))
    )
    (net (code "50") (name "unconnected-(S2-Pad4)") (class "Default")
      (node (ref "S2") (pin "4") (pinfunction "4_4") (pintype "passive+no_connect"))
    )
    (net (code "51") (name "unconnected-(S4-Pad2)") (class "Default")
      (node (ref "S4") (pin "2") (pinfunction "2_2") (pintype "passive+no_connect"))
    )
    (net (code "52") (name "unconnected-(S4-Pad4)") (class "Default")
      (node (ref "S4") (pin "4") (pinfunction "4_4") (pintype "passive+no_connect"))
    )
    (net (code "53") (name "unconnected-(S5-Pad2)") (class "Default")
      (node (ref "S5") (pin "2") (pinfunction "2_2") (pintype "passive+no_connect"))
    )
    (net (code "54") (name "unconnected-(S5-Pad4)") (class "Default")
      (node (ref "S5") (pin "4") (pinfunction "4_4") (pintype "passive+no_connect"))
    )
    (net (code "55") (name "unconnected-(S6-Pad2)") (class "Default")
      (node (ref "S6") (pin "2") (pinfunction "2_2") (pintype "passive+no_connect"))
    )
    (net (code "56") (name "unconnected-(S6-Pad4)") (class "Default")
      (node (ref "S6") (pin "4") (pinfunction "4_4") (pintype "passive+no_connect"))
    )
    (net (code "57") (name "unconnected-(S7-Pad2)") (class "Default")
      (node (ref "S7") (pin "2") (pinfunction "2_2") (pintype "passive+no_connect"))
    )
    (net (code "58") (name "unconnected-(S7-Pad4)") (class "Default")
      (node (ref "S7") (pin "4") (pinfunction "4_4") (pintype "passive+no_connect"))
    )
    (net (code "59") (name "unconnected-(VR1-NC-Pad4)") (class "Default")
      (node (ref "VR1") (pin "4") (pinfunction "NC_4") (pintype "passive+no_connect"))
    )
    (net (code "60") (name "unconnected-(VR1-NC-Pad5)") (class "Default")
      (node (ref "VR1") (pin "5") (pinfunction "NC_5") (pintype "passive+no_connect"))
    )
    (net (code "61") (name "unconnected-(VR1-NC-Pad6)") (class "Default")
      (node (ref "VR1") (pin "6") (pinfunction "NC_6") (pintype "passive+no_connect"))
    )
    (net (code "62") (name "unconnected-(VR1-NC-Pad7)") (class "Default")
      (node (ref "VR1") (pin "7") (pinfunction "NC_7") (pintype "passive+no_connect"))
    )
  )
)
